# XMAS_2023_SCH.net
KiCad netlist of a schematic drawn in Altium Designer
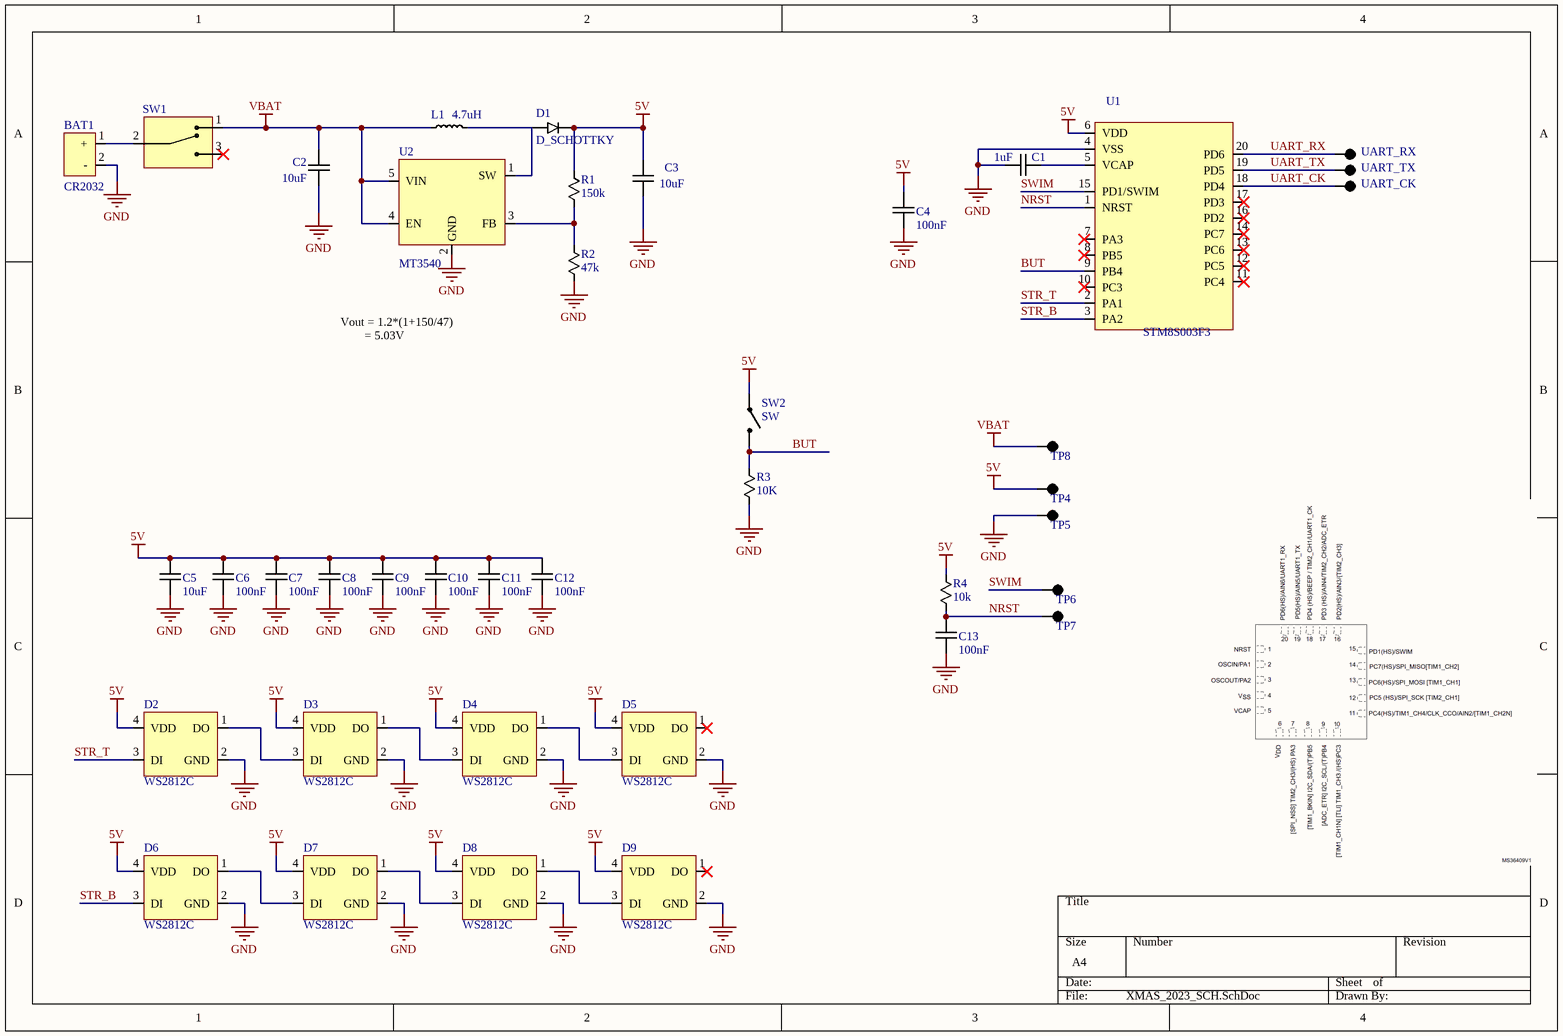
[diagram p0: XMAS_2023_SCH.SchDoc]

(export (version "E")
  (design (tool "Eeschema 10.0.6"))
  (components
    (comp (ref "BAT1")
      (value "CR2032")
      (footprint "BAT_2032")
      (fields
        (field (name "MANUFACTURER") "MYOUNG")
        (field (name "MANUFACTURER PART NUMBER") "MY-2032-12")
        (field (name "JLCPCB PART NUMBER") "C964833")
      )
      (libsource (lib "XMAS_2023_schlib") (part "BAT_CR2032"))
    )
    (comp (ref "C1")
      (value "1uF")
      (footprint "CAP_0805_NOM")
      (libsource (lib "XMAS_2023_schlib") (part "CAP_0805_10V"))
    )
    (comp (ref "C2")
      (value "10uF")
      (footprint "CAP_0805_NOM")
      (libsource (lib "XMAS_2023_schlib") (part "CAP_0805_10V"))
    )
    (comp (ref "C3")
      (value "10uF")
      (footprint "CAP_0805_NOM")
      (libsource (lib "XMAS_2023_schlib") (part "CAP_0805_10V"))
    )
    (comp (ref "C4")
      (value "100nF")
      (footprint "CAP_0805_NOM")
      (libsource (lib "XMAS_2023_schlib") (part "CAP_0805_10V"))
    )
    (comp (ref "C5")
      (value "10uF")
      (footprint "CAP_0805_NOM")
      (libsource (lib "XMAS_2023_schlib") (part "CAP_0805_10V"))
    )
    (comp (ref "C6")
      (value "100nF")
      (footprint "CAP_0805_NOM")
      (libsource (lib "XMAS_2023_schlib") (part "CAP_0805_10V"))
    )
    (comp (ref "C7")
      (value "100nF")
      (footprint "CAP_0805_NOM")
      (libsource (lib "XMAS_2023_schlib") (part "CAP_0805_10V"))
    )
    (comp (ref "C8")
      (value "100nF")
      (footprint "CAP_0805_NOM")
      (libsource (lib "XMAS_2023_schlib") (part "CAP_0805_10V"))
    )
    (comp (ref "C9")
      (value "100nF")
      (footprint "CAP_0805_NOM")
      (libsource (lib "XMAS_2023_schlib") (part "CAP_0805_10V"))
    )
    (comp (ref "C10")
      (value "100nF")
      (footprint "CAP_0805_NOM")
      (libsource (lib "XMAS_2023_schlib") (part "CAP_0805_10V"))
    )
    (comp (ref "C11")
      (value "100nF")
      (footprint "CAP_0805_NOM")
      (libsource (lib "XMAS_2023_schlib") (part "CAP_0805_10V"))
    )
    (comp (ref "C12")
      (value "100nF")
      (footprint "CAP_0805_NOM")
      (libsource (lib "XMAS_2023_schlib") (part "CAP_0805_10V"))
    )
    (comp (ref "C13")
      (value "100nF")
      (footprint "CAP_0805_NOM")
      (libsource (lib "XMAS_2023_schlib") (part "CAP_0805_10V"))
    )
    (comp (ref "D1")
      (value "D_SCHOTTKY")
      (footprint "SOD-523")
      (description "30V 500mV@200mA 200mA SOD-523 Schottky Barrier Diodes (SBD) ROHS")
      (fields (field (name "MANUFACTURER") "onsemi") (field (name "MANUFACTURER PART NUMBER") "RB521S30T1G"))
      (libsource (lib "XMAS_2023_schlib") (part "D_SCHOTTKY"))
    )
    (comp (ref "D2")
      (value "WS2812C")
      (footprint "LED_RGB_WS2812C-2020")
      (description "RGB SMD,2x2mm Light Emitting Diodes (LED) ROHS")
      (fields
        (field (name "MANUFACTURER") "Worldsemi")
        (field (name "MANUFACTURER PART NUMBER") "WS2812C-2020-V1")
      )
      (libsource (lib "XMAS_2023_schlib") (part "LED_RGB_WS2812C-2020"))
    )
    (comp (ref "D3")
      (value "WS2812C")
      (footprint "LED_RGB_WS2812C-2020")
      (description "RGB SMD,2x2mm Light Emitting Diodes (LED) ROHS")
      (fields
        (field (name "MANUFACTURER") "Worldsemi")
        (field (name "MANUFACTURER PART NUMBER") "WS2812C-2020-V1")
      )
      (libsource (lib "XMAS_2023_schlib") (part "LED_RGB_WS2812C-2020"))
    )
    (comp (ref "D4")
      (value "WS2812C")
      (footprint "LED_RGB_WS2812C-2020")
      (description "RGB SMD,2x2mm Light Emitting Diodes (LED) ROHS")
      (fields
        (field (name "MANUFACTURER") "Worldsemi")
        (field (name "MANUFACTURER PART NUMBER") "WS2812C-2020-V1")
      )
      (libsource (lib "XMAS_2023_schlib") (part "LED_RGB_WS2812C-2020"))
    )
    (comp (ref "D5")
      (value "WS2812C")
      (footprint "LED_RGB_WS2812C-2020")
      (description "RGB SMD,2x2mm Light Emitting Diodes (LED) ROHS")
      (fields
        (field (name "MANUFACTURER") "Worldsemi")
        (field (name "MANUFACTURER PART NUMBER") "WS2812C-2020-V1")
      )
      (libsource (lib "XMAS_2023_schlib") (part "LED_RGB_WS2812C-2020"))
    )
    (comp (ref "D6")
      (value "WS2812C")
      (footprint "LED_RGB_WS2812C-2020")
      (description "RGB SMD,2x2mm Light Emitting Diodes (LED) ROHS")
      (fields
        (field (name "MANUFACTURER") "Worldsemi")
        (field (name "MANUFACTURER PART NUMBER") "WS2812C-2020-V1")
      )
      (libsource (lib "XMAS_2023_schlib") (part "LED_RGB_WS2812C-2020"))
    )
    (comp (ref "D7")
      (value "WS2812C")
      (footprint "LED_RGB_WS2812C-2020")
      (description "RGB SMD,2x2mm Light Emitting Diodes (LED) ROHS")
      (fields
        (field (name "MANUFACTURER") "Worldsemi")
        (field (name "MANUFACTURER PART NUMBER") "WS2812C-2020-V1")
      )
      (libsource (lib "XMAS_2023_schlib") (part "LED_RGB_WS2812C-2020"))
    )
    (comp (ref "D8")
      (value "WS2812C")
      (footprint "LED_RGB_WS2812C-2020")
      (description "RGB SMD,2x2mm Light Emitting Diodes (LED) ROHS")
      (fields
        (field (name "MANUFACTURER") "Worldsemi")
        (field (name "MANUFACTURER PART NUMBER") "WS2812C-2020-V1")
      )
      (libsource (lib "XMAS_2023_schlib") (part "LED_RGB_WS2812C-2020"))
    )
    (comp (ref "D9")
      (value "WS2812C")
      (footprint "LED_RGB_WS2812C-2020")
      (description "RGB SMD,2x2mm Light Emitting Diodes (LED) ROHS")
      (fields
        (field (name "MANUFACTURER") "Worldsemi")
        (field (name "MANUFACTURER PART NUMBER") "WS2812C-2020-V1")
      )
      (libsource (lib "XMAS_2023_schlib") (part "LED_RGB_WS2812C-2020"))
    )
    (comp (ref "L1")
      (value "4.7uH")
      (footprint "CAP_0805_NOM")
      (description "350mA 4.7uH ±20% 400mΩ 0805 Inductors (SMD) ROHS")
      (fields
        (field (name "MANUFACTURER") "FH (Guangdong Fenghua Advanced Tech)")
        (field (name "MANUFACTURER PART NUMBER") "CMP201209UD4R7MT")
      )
      (libsource (lib "XMAS_2023_schlib") (part "IND_4.7uH_0805"))
    )
    (comp (ref "R1")
      (value "150k")
      (footprint "RES_0805_nom")
      (libsource (lib "XMAS_2023_schlib") (part "RES_0805"))
    )
    (comp (ref "R2")
      (value "47k")
      (footprint "RES_0805_nom")
      (libsource (lib "XMAS_2023_schlib") (part "RES_0805"))
    )
    (comp (ref "R3")
      (value "10K")
      (footprint "RES_0805_nom")
      (libsource (lib "XMAS_2023_schlib") (part "RES_0805"))
    )
    (comp (ref "R4")
      (value "10k")
      (footprint "RES_0805_nom")
      (libsource (lib "XMAS_2023_schlib") (part "RES_0805"))
    )
    (comp (ref "SW1")
      (value "SW_SLIDE_SPDT_MK-12C02-G025")
      (footprint "SW_SLIDE_SPDT_MK-12C02-G025")
      (fields
        (field (name "MANUFACTURER") "G-Switch")
        (field (name "MANUFACTURER PART NUMBER") "MK-12C02-G025")
        (field (name "JLCPCB PART NUMBER") "C778186")
      )
      (libsource (lib "XMAS_2023_schlib") (part "SW_SLIDE_SPDT_MK-12C02-G025"))
    )
    (comp (ref "SW2")
      (value "SW")
      (footprint "SW_TACT_SPST_TS-1187A")
      (description "No NO 50mA 100000 Times 160gf 12V Brick nogging SPST SMD Tactile Switches ROHS")
      (fields
        (field (name "MANUFACTURER") "XKB Connectivity")
        (field (name "MANUFACTURER PART NUMBER") "TS-1187A-B-A-B")
      )
      (libsource (lib "XMAS_2023_schlib") (part "SW_SPST_TACT_TS_1187A"))
    )
    (comp (ref "TP1")
      (value "UART_RX")
      (footprint "testpoint")
      (description "1.2mm Test point")
      (libsource (lib "XMAS_2023_schlib") (part "TESTPOINT"))
    )
    (comp (ref "TP2")
      (value "UART_TX")
      (footprint "testpoint")
      (description "1.2mm Test point")
      (libsource (lib "XMAS_2023_schlib") (part "TESTPOINT"))
    )
    (comp (ref "TP3")
      (value "UART_CK")
      (footprint "testpoint")
      (description "1.2mm Test point")
      (libsource (lib "XMAS_2023_schlib") (part "TESTPOINT"))
    )
    (comp (ref "TP4")
      (value "TESTPOINT")
      (footprint "testpoint")
      (description "1.2mm Test point")
      (libsource (lib "XMAS_2023_schlib") (part "TESTPOINT"))
    )
    (comp (ref "TP5")
      (value "TESTPOINT")
      (footprint "testpoint")
      (description "1.2mm Test point")
      (libsource (lib "XMAS_2023_schlib") (part "TESTPOINT"))
    )
    (comp (ref "TP6")
      (value "TESTPOINT")
      (footprint "testpoint")
      (description "1.2mm Test point")
      (libsource (lib "XMAS_2023_schlib") (part "TESTPOINT"))
    )
    (comp (ref "TP7")
      (value "TESTPOINT")
      (footprint "testpoint")
      (description "1.2mm Test point")
      (libsource (lib "XMAS_2023_schlib") (part "TESTPOINT"))
    )
    (comp (ref "TP8")
      (value "TESTPOINT")
      (footprint "testpoint")
      (description "1.2mm Test point")
      (libsource (lib "XMAS_2023_schlib") (part "TESTPOINT"))
    )
    (comp (ref "U1")
      (value "STM8S003F3")
      (footprint "UFQFPN20")
      (description "8KB 2.95V~5.5V STM8 1KB 16MHz FLASH 16 UFQFPN-20(3x3) Microcontroller Units (MCUs/MPUs/SOCs) ROHS")
      (fields
        (field (name "MANUFACTURER") "STMicroelectronics")
        (field (name "MANUFACTURER PART NUMBER") "STM8S003F3U6TR")
      )
      (libsource (lib "XMAS_2023_schlib") (part "STM8S003F3"))
    )
    (comp (ref "U2")
      (value "MT3540")
      (footprint "SOT-23 - 5")
      (description "boost converterType 28V 2.5V~5.5V 1.5A SOT-23-5 DC-DC Converters ROHS")
      (fields
        (field (name "MANUFACTURER") "XI'AN Aerosemi Tech")
        (field (name "JLCPCB PART NUMBER") "C181744")
      )
      (libsource (lib "XMAS_2023_schlib") (part "IC_BOOST_MT3540"))
    )
  )
  (nets
    (net (code "1") (name "/BUT") (class "Default")
      (node (ref "R3") (pin "2") (pinfunction "2_2") (pintype "passive"))
      (node (ref "SW2") (pin "2") (pinfunction "2_2") (pintype "passive"))
      (node (ref "U1") (pin "9") (pinfunction "PB4_9") (pintype "passive"))
    )
    (net (code "2") (name "/NRST") (class "Default")
      (node (ref "C13") (pin "2") (pinfunction "2_2") (pintype "passive"))
      (node (ref "R4") (pin "1") (pinfunction "1_1") (pintype "passive"))
      (node (ref "TP7") (pin "1") (pinfunction "1_1") (pintype "passive"))
      (node (ref "U1") (pin "1") (pinfunction "NRST_1") (pintype "passive"))
    )
    (net (code "3") (name "/STR_B") (class "Default")
      (node (ref "D6") (pin "3") (pinfunction "DI_3") (pintype "passive"))
      (node (ref "U1") (pin "3") (pinfunction "PA2_3") (pintype "passive"))
    )
    (net (code "4") (name "/STR_T") (class "Default")
      (node (ref "D2") (pin "3") (pinfunction "DI_3") (pintype "passive"))
      (node (ref "U1") (pin "2") (pinfunction "PA1_2") (pintype "passive"))
    )
    (net (code "5") (name "/SWIM") (class "Default")
      (node (ref "TP6") (pin "1") (pinfunction "1_1") (pintype "passive"))
      (node (ref "U1") (pin "15") (pinfunction "PD1/SWIM_15") (pintype "passive"))
    )
    (net (code "6") (name "/UART_CK") (class "Default")
      (node (ref "TP3") (pin "1") (pinfunction "1_1") (pintype "passive"))
      (node (ref "U1") (pin "18") (pinfunction "PD4_18") (pintype "passive"))
    )
    (net (code "7") (name "/UART_RX") (class "Default")
      (node (ref "TP1") (pin "1") (pinfunction "1_1") (pintype "passive"))
      (node (ref "U1") (pin "20") (pinfunction "PD6_20") (pintype "passive"))
    )
    (net (code "8") (name "/UART_TX") (class "Default")
      (node (ref "TP2") (pin "1") (pinfunction "1_1") (pintype "passive"))
      (node (ref "U1") (pin "19") (pinfunction "PD5_19") (pintype "passive"))
    )
    (net (code "9") (name "5V") (class "Default")
      (node (ref "C10") (pin "2") (pinfunction "2_2") (pintype "passive"))
      (node (ref "C11") (pin "2") (pinfunction "2_2") (pintype "passive"))
      (node (ref "C12") (pin "2") (pinfunction "2_2") (pintype "passive"))
      (node (ref "C3") (pin "2") (pinfunction "2_2") (pintype "passive"))
      (node (ref "C4") (pin "2") (pinfunction "2_2") (pintype "passive"))
      (node (ref "C5") (pin "2") (pinfunction "2_2") (pintype "passive"))
      (node (ref "C6") (pin "2") (pinfunction "2_2") (pintype "passive"))
      (node (ref "C7") (pin "2") (pinfunction "2_2") (pintype "passive"))
      (node (ref "C8") (pin "2") (pinfunction "2_2") (pintype "passive"))
      (node (ref "C9") (pin "2") (pinfunction "2_2") (pintype "passive"))
      (node (ref "D1") (pin "1") (pinfunction "Cathode_1") (pintype "passive"))
      (node (ref "D2") (pin "4") (pinfunction "VDD_4") (pintype "passive"))
      (node (ref "D3") (pin "4") (pinfunction "VDD_4") (pintype "passive"))
      (node (ref "D4") (pin "4") (pinfunction "VDD_4") (pintype "passive"))
      (node (ref "D5") (pin "4") (pinfunction "VDD_4") (pintype "passive"))
      (node (ref "D6") (pin "4") (pinfunction "VDD_4") (pintype "passive"))
      (node (ref "D7") (pin "4") (pinfunction "VDD_4") (pintype "passive"))
      (node (ref "D8") (pin "4") (pinfunction "VDD_4") (pintype "passive"))
      (node (ref "D9") (pin "4") (pinfunction "VDD_4") (pintype "passive"))
      (node (ref "R1") (pin "2") (pinfunction "2_2") (pintype "passive"))
      (node (ref "R4") (pin "2") (pinfunction "2_2") (pintype "passive"))
      (node (ref "SW2") (pin "1") (pinfunction "1_1") (pintype "passive"))
      (node (ref "TP4") (pin "1") (pinfunction "1_1") (pintype "passive"))
      (node (ref "U1") (pin "6") (pinfunction "VDD_6") (pintype "passive"))
    )
    (net (code "10") (name "GND") (class "Default")
      (node (ref "BAT1") (pin "2") (pinfunction "-_2") (pintype "passive"))
      (node (ref "C1") (pin "1") (pinfunction "1_1") (pintype "passive"))
      (node (ref "C10") (pin "1") (pinfunction "1_1") (pintype "passive"))
      (node (ref "C11") (pin "1") (pinfunction "1_1") (pintype "passive"))
      (node (ref "C12") (pin "1") (pinfunction "1_1") (pintype "passive"))
      (node (ref "C13") (pin "1") (pinfunction "1_1") (pintype "passive"))
      (node (ref "C2") (pin "1") (pinfunction "1_1") (pintype "passive"))
      (node (ref "C3") (pin "1") (pinfunction "1_1") (pintype "passive"))
      (node (ref "C4") (pin "1") (pinfunction "1_1") (pintype "passive"))
      (node (ref "C5") (pin "1") (pinfunction "1_1") (pintype "passive"))
      (node (ref "C6") (pin "1") (pinfunction "1_1") (pintype "passive"))
      (node (ref "C7") (pin "1") (pinfunction "1_1") (pintype "passive"))
      (node (ref "C8") (pin "1") (pinfunction "1_1") (pintype "passive"))
      (node (ref "C9") (pin "1") (pinfunction "1_1") (pintype "passive"))
      (node (ref "D2") (pin "2") (pinfunction "GND_2") (pintype "passive"))
      (node (ref "D3") (pin "2") (pinfunction "GND_2") (pintype "passive"))
      (node (ref "D4") (pin "2") (pinfunction "GND_2") (pintype "passive"))
      (node (ref "D5") (pin "2") (pinfunction "GND_2") (pintype "passive"))
      (node (ref "D6") (pin "2") (pinfunction "GND_2") (pintype "passive"))
      (node (ref "D7") (pin "2") (pinfunction "GND_2") (pintype "passive"))
      (node (ref "D8") (pin "2") (pinfunction "GND_2") (pintype "passive"))
      (node (ref "D9") (pin "2") (pinfunction "GND_2") (pintype "passive"))
      (node (ref "R2") (pin "1") (pinfunction "1_1") (pintype "passive"))
      (node (ref "R3") (pin "1") (pinfunction "1_1") (pintype "passive"))
      (node (ref "TP5") (pin "1") (pinfunction "1_1") (pintype "passive"))
      (node (ref "U1") (pin "4") (pinfunction "VSS_4") (pintype "passive"))
      (node (ref "U2") (pin "2") (pinfunction "GND_2") (pintype "passive"))
    )
    (net (code "11") (name "Net-(BAT1-+)") (class "Default")
      (node (ref "BAT1") (pin "1") (pinfunction "+_1") (pintype "passive"))
      (node (ref "SW1") (pin "2") (pinfunction "COM_2") (pintype "passive"))
    )
    (net (code "12") (name "Net-(D1-Anode)") (class "Default")
      (node (ref "D1") (pin "2") (pinfunction "Anode_2") (pintype "passive"))
      (node (ref "L1") (pin "2") (pinfunction "2_2") (pintype "passive"))
      (node (ref "U2") (pin "1") (pinfunction "SW_1") (pintype "passive"))
    )
    (net (code "13") (name "Net-(D2-DO)") (class "Default")
      (node (ref "D2") (pin "1") (pinfunction "DO_1") (pintype "passive"))
      (node (ref "D3") (pin "3") (pinfunction "DI_3") (pintype "passive"))
    )
    (net (code "14") (name "Net-(D3-DO)") (class "Default")
      (node (ref "D3") (pin "1") (pinfunction "DO_1") (pintype "passive"))
      (node (ref "D4") (pin "3") (pinfunction "DI_3") (pintype "passive"))
    )
    (net (code "15") (name "Net-(D4-DO)") (class "Default")
      (node (ref "D4") (pin "1") (pinfunction "DO_1") (pintype "passive"))
      (node (ref "D5") (pin "3") (pinfunction "DI_3") (pintype "passive"))
    )
    (net (code "16") (name "Net-(D6-DO)") (class "Default")
      (node (ref "D6") (pin "1") (pinfunction "DO_1") (pintype "passive"))
      (node (ref "D7") (pin "3") (pinfunction "DI_3") (pintype "passive"))
    )
    (net (code "17") (name "Net-(D7-DO)") (class "Default")
      (node (ref "D7") (pin "1") (pinfunction "DO_1") (pintype "passive"))
      (node (ref "D8") (pin "3") (pinfunction "DI_3") (pintype "passive"))
    )
    (net (code "18") (name "Net-(D8-DO)") (class "Default")
      (node (ref "D8") (pin "1") (pinfunction "DO_1") (pintype "passive"))
      (node (ref "D9") (pin "3") (pinfunction "DI_3") (pintype "passive"))
    )
    (net (code "19") (name "Net-(U1-VCAP)") (class "Default")
      (node (ref "C1") (pin "2") (pinfunction "2_2") (pintype "passive"))
      (node (ref "U1") (pin "5") (pinfunction "VCAP_5") (pintype "passive"))
    )
    (net (code "20") (name "Net-(U2-FB)") (class "Default")
      (node (ref "R1") (pin "1") (pinfunction "1_1") (pintype "passive"))
      (node (ref "R2") (pin "2") (pinfunction "2_2") (pintype "passive"))
      (node (ref "U2") (pin "3") (pinfunction "FB_3") (pintype "passive"))
    )
    (net (code "21") (name "VBAT") (class "Default")
      (node (ref "C2") (pin "2") (pinfunction "2_2") (pintype "passive"))
      (node (ref "L1") (pin "1") (pinfunction "1_1") (pintype "passive"))
      (node (ref "SW1") (pin "1") (pinfunction "A_1") (pintype "passive"))
      (node (ref "TP8") (pin "1") (pinfunction "1_1") (pintype "passive"))
      (node (ref "U2") (pin "4") (pinfunction "EN_4") (pintype "passive"))
      (node (ref "U2") (pin "5") (pinfunction "VIN_5") (pintype "passive"))
    )
    (net (code "22") (name "unconnected-(D5-DO-Pad1)") (class "Default")
      (node (ref "D5") (pin "1") (pinfunction "DO_1") (pintype "passive+no_connect"))
    )
    (net (code "23") (name "unconnected-(D9-DO-Pad1)") (class "Default")
      (node (ref "D9") (pin "1") (pinfunction "DO_1") (pintype "passive+no_connect"))
    )
    (net (code "24") (name "unconnected-(SW1-B-Pad3)") (class "Default")
      (node (ref "SW1") (pin "3") (pinfunction "B_3") (pintype "passive+no_connect"))
    )
    (net (code "25") (name "unconnected-(U1-PA3-Pad7)") (class "Default")
      (node (ref "U1") (pin "7") (pinfunction "PA3_7") (pintype "passive+no_connect"))
    )
    (net (code "26") (name "unconnected-(U1-PB5-Pad8)") (class "Default")
      (node (ref "U1") (pin "8") (pinfunction "PB5_8") (pintype "passive+no_connect"))
    )
    (net (code "27") (name "unconnected-(U1-PC3-Pad10)") (class "Default")
      (node (ref "U1") (pin "10") (pinfunction "PC3_10") (pintype "passive+no_connect"))
    )
    (net (code "28") (name "unconnected-(U1-PC4-Pad11)") (class "Default")
      (node (ref "U1") (pin "11") (pinfunction "PC4_11") (pintype "passive+no_connect"))
    )
    (net (code "29") (name "unconnected-(U1-PC5-Pad12)") (class "Default")
      (node (ref "U1") (pin "12") (pinfunction "PC5_12") (pintype "passive+no_connect"))
    )
    (net (code "30") (name "unconnected-(U1-PC6-Pad13)") (class "Default")
      (node (ref "U1") (pin "13") (pinfunction "PC6_13") (pintype "passive+no_connect"))
    )
    (net (code "31") (name "unconnected-(U1-PC7-Pad14)") (class "Default")
      (node (ref "U1") (pin "14") (pinfunction "PC7_14") (pintype "passive+no_connect"))
    )
    (net (code "32") (name "unconnected-(U1-PD2-Pad16)") (class "Default")
      (node (ref "U1") (pin "16") (pinfunction "PD2_16") (pintype "passive+no_connect"))
    )
    (net (code "33") (name "unconnected-(U1-PD3-Pad17)") (class "Default")
      (node (ref "U1") (pin "17") (pinfunction "PD3_17") (pintype "passive+no_connect"))
    )
  )
)
